# PCB_AMR_Esquematico.net
KiCad netlist of a schematic drawn in EasyEDA
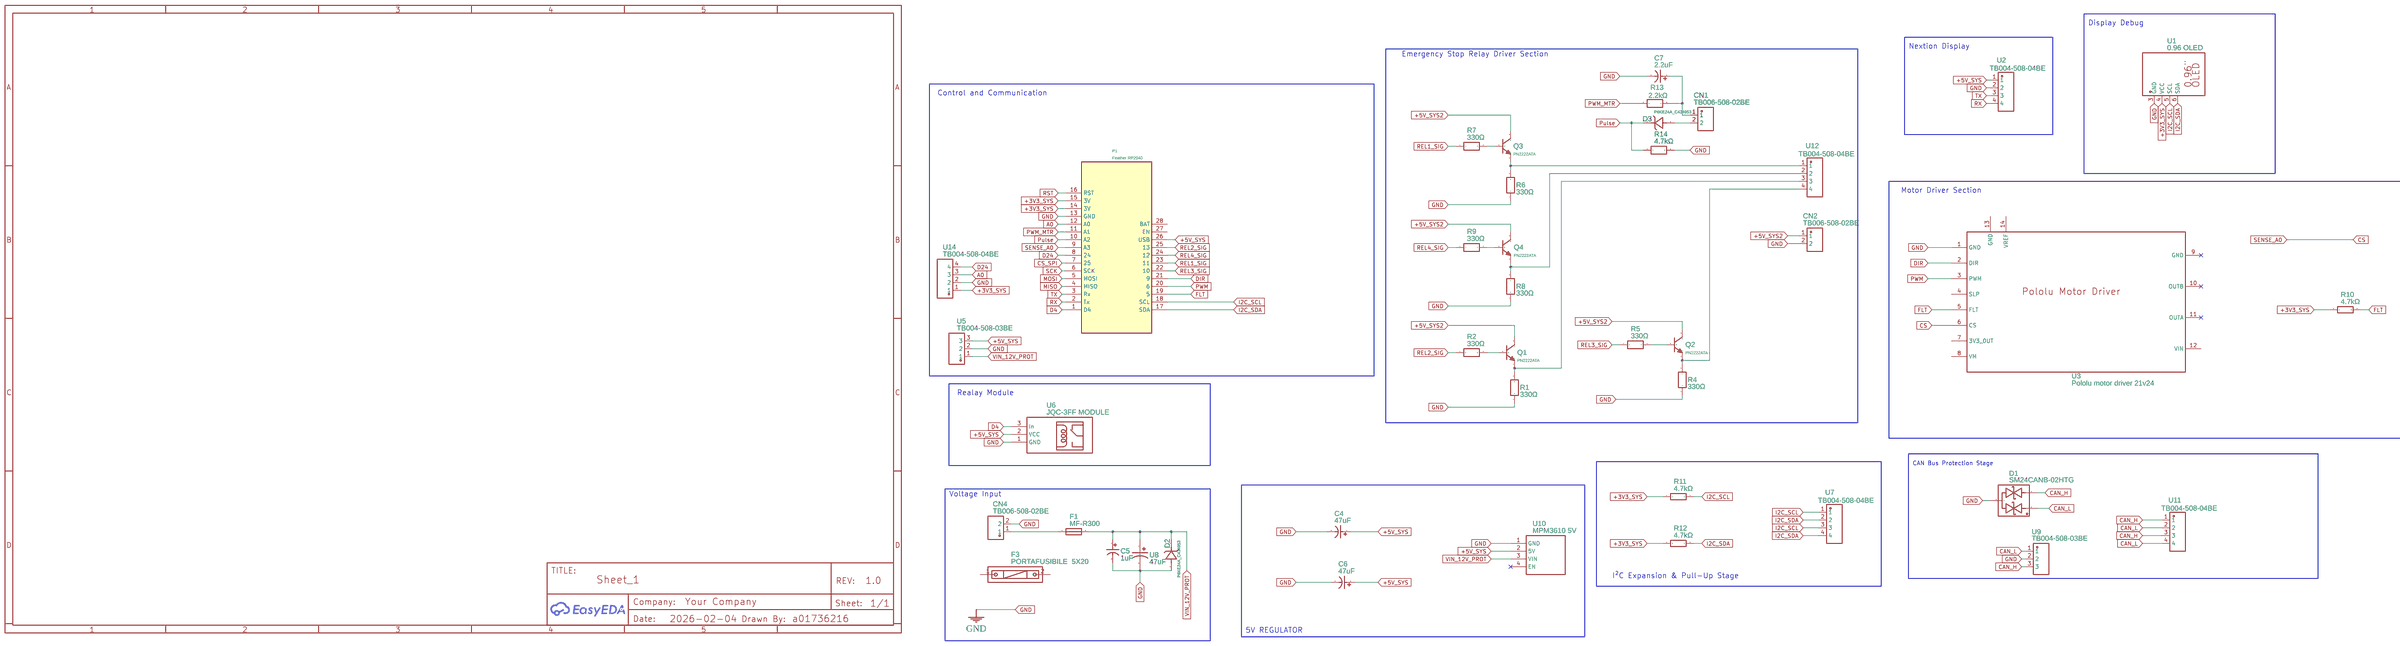
[diagram p0: schematic sheet]

(export (version "E")
  (design (tool "Eeschema 10.0.6"))
  (components
    (comp (ref "C4")
      (value "47uF")
      (fields
        (field (name "Manufacturer Part") "KM476M016D11RR0VH2FP0")
        (field (name "Manufacturer") "Chengx(承兴)")
      )
      (libsource (lib "") (part "47uF 16V Aluminum electrolytic capacitors"))
    )
    (comp (ref "C5")
      (value "1uF")
      (fields
        (field (name "Manufacturer Part") "KM105M250E11RR0VH2FP0")
        (field (name "Manufacturer") "Chengx(承兴)")
      )
      (libsource (lib "") (part "1uF 250V 6.3*11"))
    )
    (comp (ref "C6")
      (value "47uF")
      (fields
        (field (name "Manufacturer Part") "KM476M016D11RR0VH2FP0")
        (field (name "Manufacturer") "Chengx(承兴)")
      )
      (libsource (lib "") (part "47uF 16V Aluminum electrolytic capacitors"))
    )
    (comp (ref "C7")
      (value "2.2uF")
      (fields
        (field (name "Manufacturer Part") "KM476M016D11RR0VH2FP0")
        (field (name "Manufacturer") "Chengx(承兴)")
      )
      (libsource (lib "") (part "47uF 16V Aluminum electrolytic capacitors"))
    )
    (comp (ref "CN1") (value "TB006-508-02BE") (libsource (lib "") (part "TB006-508-02BE_1")))
    (comp (ref "CN2") (value "TB006-508-02BE") (libsource (lib "") (part "TB006-508-02BE_1")))
    (comp (ref "CN4") (value "TB006-508-02BE") (libsource (lib "") (part "TB006-508-02BE")))
    (comp (ref "D1")
      (value "SM24CANB-02HTG")
      (fields (field (name "Manufacturer") "Littelfuse(美国力特)"))
      (libsource (lib "") (part "SM24CANB-02HTG"))
    )
    (comp (ref "D2")
      (value "P6KE24A_C434953")
      (fields (field (name "Manufacturer Part") "P6KE24A") (field (name "Manufacturer") "CREATEK(达晶微)"))
      (libsource (lib "") (part "P6KE24A_C434953_1"))
    )
    (comp (ref "D3")
      (value "P6KE24A_C434953")
      (fields (field (name "Manufacturer Part") "P6KE24A") (field (name "Manufacturer") "CREATEK(达晶微)"))
      (libsource (lib "") (part "P6KE24A_C434953"))
    )
    (comp (ref "F1")
      (value "MF-R300")
      (fields (field (name "Manufacturer") "BOURNS"))
      (libsource (lib "") (part "MF-R300"))
    )
    (comp (ref "F3") (value "PORTAFUSIBILE  5X20") (libsource (lib "") (part "PORTAFUSIBILE  5X20")))
    (comp (ref "P1")
      (value "Feather RP2040")
      (fields (field (name "Manufacturer") "Adafruit"))
      (libsource (lib "") (part "Feather RP2040"))
    )
    (comp (ref "Q1")
      (value "PN2222ATA")
      (fields (field (name "Manufacturer") "onsemi(安森美)"))
      (libsource (lib "") (part "PN2222ATA"))
    )
    (comp (ref "Q2")
      (value "PN2222ATA")
      (fields (field (name "Manufacturer") "onsemi(安森美)"))
      (libsource (lib "") (part "PN2222ATA"))
    )
    (comp (ref "Q3")
      (value "PN2222ATA")
      (fields (field (name "Manufacturer") "onsemi(安森美)"))
      (libsource (lib "") (part "PN2222ATA"))
    )
    (comp (ref "Q4")
      (value "PN2222ATA")
      (fields (field (name "Manufacturer") "onsemi(安森美)"))
      (libsource (lib "") (part "PN2222ATA"))
    )
    (comp (ref "R1")
      (value "330Ω")
      (fields
        (field (name "Manufacturer Part") "RN 1/4W 330R F T/B A1")
        (field (name "Manufacturer") "Tyohm(幸亚电阻)")
      )
      (libsource (lib "") (part "RN 1/4W 330R F T/B A1_1"))
    )
    (comp (ref "R2")
      (value "330Ω")
      (fields
        (field (name "Manufacturer Part") "RN 1/4W 330R F T/B A1")
        (field (name "Manufacturer") "Tyohm(幸亚电阻)")
      )
      (libsource (lib "") (part "RN 1/4W 330R F T/B A1"))
    )
    (comp (ref "R4")
      (value "330Ω")
      (fields
        (field (name "Manufacturer Part") "RN 1/4W 330R F T/B A1")
        (field (name "Manufacturer") "Tyohm(幸亚电阻)")
      )
      (libsource (lib "") (part "RN 1/4W 330R F T/B A1_1"))
    )
    (comp (ref "R5")
      (value "330Ω")
      (fields
        (field (name "Manufacturer Part") "RN 1/4W 330R F T/B A1")
        (field (name "Manufacturer") "Tyohm(幸亚电阻)")
      )
      (libsource (lib "") (part "RN 1/4W 330R F T/B A1"))
    )
    (comp (ref "R6")
      (value "330Ω")
      (fields
        (field (name "Manufacturer Part") "RN 1/4W 330R F T/B A1")
        (field (name "Manufacturer") "Tyohm(幸亚电阻)")
      )
      (libsource (lib "") (part "RN 1/4W 330R F T/B A1_1"))
    )
    (comp (ref "R7")
      (value "330Ω")
      (fields
        (field (name "Manufacturer Part") "RN 1/4W 330R F T/B A1")
        (field (name "Manufacturer") "Tyohm(幸亚电阻)")
      )
      (libsource (lib "") (part "RN 1/4W 330R F T/B A1"))
    )
    (comp (ref "R8")
      (value "330Ω")
      (fields
        (field (name "Manufacturer Part") "RN 1/4W 330R F T/B A1")
        (field (name "Manufacturer") "Tyohm(幸亚电阻)")
      )
      (libsource (lib "") (part "RN 1/4W 330R F T/B A1_1"))
    )
    (comp (ref "R9")
      (value "330Ω")
      (fields
        (field (name "Manufacturer Part") "RN 1/4W 330R F T/B A1")
        (field (name "Manufacturer") "Tyohm(幸亚电阻)")
      )
      (libsource (lib "") (part "RN 1/4W 330R F T/B A1"))
    )
    (comp (ref "R10")
      (value "4.7kΩ")
      (fields
        (field (name "Manufacturer Part") "CF1/4W-4.7KΩ±5% T")
        (field (name "Manufacturer") "CCO(千志电子)")
      )
      (libsource (lib "") (part "CF1/4W-4.7KΩ±5% T52"))
    )
    (comp (ref "R11")
      (value "4.7kΩ")
      (fields
        (field (name "Manufacturer Part") "CF1/4W-4.7KΩ±5% T")
        (field (name "Manufacturer") "CCO(千志电子)")
      )
      (libsource (lib "") (part "CF1/4W-4.7KΩ±5% T52"))
    )
    (comp (ref "R12")
      (value "4.7kΩ")
      (fields
        (field (name "Manufacturer Part") "CF1/4W-4.7KΩ±5% T")
        (field (name "Manufacturer") "CCO(千志电子)")
      )
      (libsource (lib "") (part "CF1/4W-4.7KΩ±5% T52"))
    )
    (comp (ref "R13")
      (value "2.2kΩ")
      (fields
        (field (name "Manufacturer Part") "RN 1/4W 330R F T/B A1")
        (field (name "Manufacturer") "Tyohm(幸亚电阻)")
      )
      (libsource (lib "") (part "RN 1/4W 330R F T/B A1"))
    )
    (comp (ref "R14")
      (value "4.7kΩ")
      (fields
        (field (name "Manufacturer Part") "RN 1/4W 330R F T/B A1")
        (field (name "Manufacturer") "Tyohm(幸亚电阻)")
      )
      (libsource (lib "") (part "RN 1/4W 330R F T/B A1"))
    )
    (comp (ref "U1")
      (value "0.96 OLED")
      (fields
        (field (name "Manufacturer Part") "ZJY096S0700BG01蓝色")
        (field (name "Manufacturer") "AZDelivery")
      )
      (libsource (lib "") (part "0.96 OLED"))
    )
    (comp (ref "U2")
      (value "TB004-508-04BE")
      (fields (field (name "Manufacturer") "CUI"))
      (libsource (lib "") (part "TB004-508-04BE"))
    )
    (comp (ref "U3")
      (value "Pololu motor driver 21v24")
      (libsource (lib "") (part "Pololu motor driver 18v25"))
    )
    (comp (ref "U5")
      (value "TB004-508-03BE")
      (fields (field (name "Manufacturer") "CUI"))
      (libsource (lib "") (part "TB004-508-03BE_1"))
    )
    (comp (ref "U6")
      (value "JQC-3FF MODULE")
      (fields (field (name "Manufacturer Part") "JQC-3FF"))
      (libsource (lib "") (part "JQC-3FF MODULE"))
    )
    (comp (ref "U7")
      (value "TB004-508-04BE")
      (fields (field (name "Manufacturer") "CUI"))
      (libsource (lib "") (part "TB004-508-04BE"))
    )
    (comp (ref "U8")
      (value "47uF")
      (fields (field (name "Manufacturer Part") "25V47uF CD110") (field (name "Manufacturer") "HRK(鸿瑞凯电子)"))
      (libsource (lib "") (part "25V47UF CD110"))
    )
    (comp (ref "U9")
      (value "TB004-508-03BE")
      (fields (field (name "Manufacturer") "CUI"))
      (libsource (lib "") (part "TB004-508-03BE"))
    )
    (comp (ref "U10")
      (value "MPM3610 5V")
      (fields (field (name "Manufacturer Part") "4739") (field (name "Manufacturer") "Adafruit"))
      (libsource (lib "") (part "MPM3610 5V"))
    )
    (comp (ref "U11")
      (value "TB004-508-04BE")
      (fields (field (name "Manufacturer") "CUI"))
      (libsource (lib "") (part "TB004-508-04BE"))
    )
    (comp (ref "U12")
      (value "TB004-508-04BE")
      (fields (field (name "Manufacturer") "CUI"))
      (libsource (lib "") (part "TB004-508-04BE"))
    )
    (comp (ref "U14")
      (value "TB004-508-04BE")
      (fields (field (name "Manufacturer") "CUI"))
      (libsource (lib "") (part "TB004-508-04BE_1"))
    )
  )
  (nets
    (net (code "1") (name "+3V3_SYS") (class "Default")
      (node (ref "P1") (pin "14") (pinfunction "3V_14") (pintype "unspecified"))
      (node (ref "P1") (pin "15") (pinfunction "3V_15") (pintype "unspecified"))
      (node (ref "R10") (pin "1") (pinfunction "1_1") (pintype "unspecified"))
      (node (ref "R11") (pin "1") (pinfunction "1_1") (pintype "unspecified"))
      (node (ref "R12") (pin "1") (pinfunction "1_1") (pintype "unspecified"))
      (node (ref "U1") (pin "4") (pinfunction "VCC_4") (pintype "unspecified"))
      (node (ref "U14") (pin "1") (pinfunction "1_1") (pintype "unspecified"))
    )
    (net (code "2") (name "+5V_SYS") (class "Default")
      (node (ref "C4") (pin "1") (pinfunction "1_1") (pintype "input"))
      (node (ref "C6") (pin "1") (pinfunction "1_1") (pintype "input"))
      (node (ref "P1") (pin "26") (pinfunction "USB_26") (pintype "unspecified"))
      (node (ref "U10") (pin "2") (pinfunction "5V_2") (pintype "unspecified"))
      (node (ref "U2") (pin "1") (pinfunction "1_1") (pintype "unspecified"))
      (node (ref "U5") (pin "3") (pinfunction "3_3") (pintype "unspecified"))
      (node (ref "U6") (pin "2") (pinfunction "VCC_2") (pintype "unspecified"))
    )
    (net (code "3") (name "+5V_SYS2") (class "Default")
      (node (ref "CN2") (pin "1") (pinfunction "1_1") (pintype "unspecified"))
      (node (ref "Q1") (pin "3") (pinfunction "C_3") (pintype "unspecified"))
      (node (ref "Q2") (pin "3") (pinfunction "C_3") (pintype "unspecified"))
      (node (ref "Q3") (pin "3") (pinfunction "C_3") (pintype "unspecified"))
      (node (ref "Q4") (pin "3") (pinfunction "C_3") (pintype "unspecified"))
    )
    (net (code "4") (name "A0") (class "Default")
      (node (ref "P1") (pin "12") (pinfunction "A0_12") (pintype "unspecified"))
      (node (ref "U14") (pin "3") (pinfunction "3_3") (pintype "unspecified"))
    )
    (net (code "5") (name "CAN_H") (class "Default")
      (node (ref "D1") (pin "2") (pinfunction "2_2") (pintype "unspecified"))
      (node (ref "U11") (pin "1") (pinfunction "1_1") (pintype "unspecified"))
      (node (ref "U11") (pin "3") (pinfunction "3_3") (pintype "unspecified"))
      (node (ref "U9") (pin "3") (pinfunction "3_3") (pintype "unspecified"))
    )
    (net (code "6") (name "CAN_L") (class "Default")
      (node (ref "D1") (pin "1") (pinfunction "1_1") (pintype "unspecified"))
      (node (ref "U11") (pin "2") (pinfunction "2_2") (pintype "unspecified"))
      (node (ref "U11") (pin "4") (pinfunction "4_4") (pintype "unspecified"))
      (node (ref "U9") (pin "1") (pinfunction "1_1") (pintype "unspecified"))
    )
    (net (code "7") (name "CS") (class "Default")
      (node (ref "P1") (pin "9") (pinfunction "A3_9") (pintype "unspecified"))
      (node (ref "U3") (pin "6") (pinfunction "CS_6") (pintype "unspecified"))
    )
    (net (code "8") (name "CS_SPI") (class "Default")
      (node (ref "P1") (pin "7") (pinfunction "25_7") (pintype "unspecified"))
    )
    (net (code "9") (name "D4") (class "Default")
      (node (ref "P1") (pin "1") (pinfunction "D4_1") (pintype "unspecified"))
      (node (ref "U6") (pin "3") (pinfunction "In_3") (pintype "unspecified"))
    )
    (net (code "10") (name "D24") (class "Default")
      (node (ref "P1") (pin "8") (pinfunction "24_8") (pintype "unspecified"))
      (node (ref "U14") (pin "4") (pinfunction "4_4") (pintype "unspecified"))
    )
    (net (code "11") (name "DIR") (class "Default")
      (node (ref "P1") (pin "21") (pinfunction "9_21") (pintype "unspecified"))
      (node (ref "U3") (pin "2") (pinfunction "DIR_2") (pintype "unspecified"))
    )
    (net (code "12") (name "FLT") (class "Default")
      (node (ref "P1") (pin "19") (pinfunction "5_19") (pintype "unspecified"))
      (node (ref "R10") (pin "2") (pinfunction "2_2") (pintype "unspecified"))
      (node (ref "U3") (pin "5") (pinfunction "FLT_5") (pintype "unspecified"))
    )
    (net (code "13") (name "GND") (class "Default")
      (node (ref "C4") (pin "2") (pinfunction "2_2") (pintype "input"))
      (node (ref "C5") (pin "2") (pinfunction "2_2") (pintype "input"))
      (node (ref "C6") (pin "2") (pinfunction "2_2") (pintype "input"))
      (node (ref "C7") (pin "2") (pinfunction "2_2") (pintype "input"))
      (node (ref "CN2") (pin "2") (pinfunction "2_2") (pintype "unspecified"))
      (node (ref "CN4") (pin "2") (pinfunction "2_2") (pintype "unspecified"))
      (node (ref "D1") (pin "3") (pinfunction "3_3") (pintype "unspecified"))
      (node (ref "D2") (pin "2") (pinfunction "A_2") (pintype "unspecified"))
      (node (ref "P1") (pin "13") (pinfunction "GND_13") (pintype "unspecified"))
      (node (ref "R1") (pin "1") (pinfunction "1_1") (pintype "unspecified"))
      (node (ref "R14") (pin "2") (pinfunction "2_2") (pintype "unspecified"))
      (node (ref "R4") (pin "1") (pinfunction "1_1") (pintype "unspecified"))
      (node (ref "R6") (pin "1") (pinfunction "1_1") (pintype "unspecified"))
      (node (ref "R8") (pin "1") (pinfunction "1_1") (pintype "unspecified"))
      (node (ref "U1") (pin "3") (pinfunction "GND_3") (pintype "unspecified"))
      (node (ref "U10") (pin "1") (pinfunction "GND_1") (pintype "unspecified"))
      (node (ref "U14") (pin "2") (pinfunction "2_2") (pintype "unspecified"))
      (node (ref "U2") (pin "2") (pinfunction "2_2") (pintype "unspecified"))
      (node (ref "U3") (pin "1") (pinfunction "GND_1") (pintype "unspecified"))
      (node (ref "U5") (pin "2") (pinfunction "2_2") (pintype "unspecified"))
      (node (ref "U6") (pin "1") (pinfunction "GND_1") (pintype "unspecified"))
      (node (ref "U8") (pin "2") (pinfunction "2_2") (pintype "unspecified"))
      (node (ref "U9") (pin "2") (pinfunction "2_2") (pintype "unspecified"))
    )
    (net (code "14") (name "I2C_SCL") (class "Default")
      (node (ref "P1") (pin "18") (pinfunction "SCL_18") (pintype "unspecified"))
      (node (ref "R11") (pin "2") (pinfunction "2_2") (pintype "unspecified"))
      (node (ref "U1") (pin "5") (pinfunction "SCL_5") (pintype "unspecified"))
      (node (ref "U7") (pin "1") (pinfunction "1_1") (pintype "unspecified"))
      (node (ref "U7") (pin "3") (pinfunction "3_3") (pintype "unspecified"))
    )
    (net (code "15") (name "I2C_SDA") (class "Default")
      (node (ref "P1") (pin "17") (pinfunction "SDA_17") (pintype "unspecified"))
      (node (ref "R12") (pin "2") (pinfunction "2_2") (pintype "unspecified"))
      (node (ref "U1") (pin "6") (pinfunction "SDA_6") (pintype "unspecified"))
      (node (ref "U7") (pin "2") (pinfunction "2_2") (pintype "unspecified"))
      (node (ref "U7") (pin "4") (pinfunction "4_4") (pintype "unspecified"))
    )
    (net (code "16") (name "MISO") (class "Default")
      (node (ref "P1") (pin "4") (pinfunction "MISO_4") (pintype "unspecified"))
    )
    (net (code "17") (name "MOSI") (class "Default")
      (node (ref "P1") (pin "5") (pinfunction "MOSI_5") (pintype "unspecified"))
    )
    (net (code "18") (name "Net-(C7-Pad1)") (class "Default")
      (node (ref "C7") (pin "1") (pinfunction "1_1") (pintype "input"))
      (node (ref "CN1") (pin "1") (pinfunction "1_1") (pintype "unspecified"))
      (node (ref "R13") (pin "2") (pinfunction "2_2") (pintype "unspecified"))
    )
    (net (code "19") (name "Net-(CN4-Pad1)") (class "Default")
      (node (ref "CN4") (pin "1") (pinfunction "1_1") (pintype "unspecified"))
      (node (ref "F1") (pin "1") (pinfunction "1_1") (pintype "unspecified"))
    )
    (net (code "20") (name "Net-(D3-A)") (class "Default")
      (node (ref "CN1") (pin "2") (pinfunction "2_2") (pintype "unspecified"))
      (node (ref "D3") (pin "2") (pinfunction "A_2") (pintype "unspecified"))
    )
    (net (code "21") (name "Net-(Q1-B)") (class "Default")
      (node (ref "Q1") (pin "2") (pinfunction "B_2") (pintype "unspecified"))
      (node (ref "R2") (pin "2") (pinfunction "2_2") (pintype "unspecified"))
    )
    (net (code "22") (name "Net-(Q1-E)") (class "Default")
      (node (ref "Q1") (pin "1") (pinfunction "E_1") (pintype "unspecified"))
      (node (ref "R1") (pin "2") (pinfunction "2_2") (pintype "unspecified"))
      (node (ref "U12") (pin "3") (pinfunction "3_3") (pintype "unspecified"))
    )
    (net (code "23") (name "Net-(Q2-B)") (class "Default")
      (node (ref "Q2") (pin "2") (pinfunction "B_2") (pintype "unspecified"))
      (node (ref "R5") (pin "2") (pinfunction "2_2") (pintype "unspecified"))
    )
    (net (code "24") (name "Net-(Q2-E)") (class "Default")
      (node (ref "Q2") (pin "1") (pinfunction "E_1") (pintype "unspecified"))
      (node (ref "R4") (pin "2") (pinfunction "2_2") (pintype "unspecified"))
      (node (ref "U12") (pin "4") (pinfunction "4_4") (pintype "unspecified"))
    )
    (net (code "25") (name "Net-(Q3-B)") (class "Default")
      (node (ref "Q3") (pin "2") (pinfunction "B_2") (pintype "unspecified"))
      (node (ref "R7") (pin "2") (pinfunction "2_2") (pintype "unspecified"))
    )
    (net (code "26") (name "Net-(Q3-E)") (class "Default")
      (node (ref "Q3") (pin "1") (pinfunction "E_1") (pintype "unspecified"))
      (node (ref "R6") (pin "2") (pinfunction "2_2") (pintype "unspecified"))
      (node (ref "U12") (pin "1") (pinfunction "1_1") (pintype "unspecified"))
    )
    (net (code "27") (name "Net-(Q4-B)") (class "Default")
      (node (ref "Q4") (pin "2") (pinfunction "B_2") (pintype "unspecified"))
      (node (ref "R9") (pin "2") (pinfunction "2_2") (pintype "unspecified"))
    )
    (net (code "28") (name "Net-(Q4-E)") (class "Default")
      (node (ref "Q4") (pin "1") (pinfunction "E_1") (pintype "unspecified"))
      (node (ref "R8") (pin "2") (pinfunction "2_2") (pintype "unspecified"))
      (node (ref "U12") (pin "2") (pinfunction "2_2") (pintype "unspecified"))
    )
    (net (code "29") (name "PWM") (class "Default")
      (node (ref "P1") (pin "20") (pinfunction "6_20") (pintype "unspecified"))
      (node (ref "U3") (pin "3") (pinfunction "PWM_3") (pintype "unspecified"))
    )
    (net (code "30") (name "PWM_MTR") (class "Default")
      (node (ref "P1") (pin "11") (pinfunction "A1_11") (pintype "unspecified"))
      (node (ref "R13") (pin "1") (pinfunction "1_1") (pintype "unspecified"))
    )
    (net (code "31") (name "Pulse") (class "Default")
      (node (ref "D3") (pin "1") (pinfunction "C_1") (pintype "unspecified"))
      (node (ref "P1") (pin "10") (pinfunction "A2_10") (pintype "unspecified"))
      (node (ref "R14") (pin "1") (pinfunction "1_1") (pintype "unspecified"))
    )
    (net (code "32") (name "REL1_SIG") (class "Default")
      (node (ref "P1") (pin "23") (pinfunction "11_23") (pintype "unspecified"))
      (node (ref "R7") (pin "1") (pinfunction "1_1") (pintype "unspecified"))
    )
    (net (code "33") (name "REL2_SIG") (class "Default")
      (node (ref "P1") (pin "25") (pinfunction "13_25") (pintype "unspecified"))
      (node (ref "R2") (pin "1") (pinfunction "1_1") (pintype "unspecified"))
    )
    (net (code "34") (name "REL3_SIG") (class "Default")
      (node (ref "P1") (pin "22") (pinfunction "10_22") (pintype "unspecified"))
      (node (ref "R5") (pin "1") (pinfunction "1_1") (pintype "unspecified"))
    )
    (net (code "35") (name "REL4_SIG") (class "Default")
      (node (ref "P1") (pin "24") (pinfunction "12_24") (pintype "unspecified"))
      (node (ref "R9") (pin "1") (pinfunction "1_1") (pintype "unspecified"))
    )
    (net (code "36") (name "RST") (class "Default")
      (node (ref "P1") (pin "16") (pinfunction "RST_16") (pintype "unspecified"))
    )
    (net (code "37") (name "RX") (class "Default")
      (node (ref "P1") (pin "2") (pinfunction "Tx_2") (pintype "unspecified"))
      (node (ref "U2") (pin "4") (pinfunction "4_4") (pintype "unspecified"))
    )
    (net (code "38") (name "SCK") (class "Default")
      (node (ref "P1") (pin "6") (pinfunction "SCK_6") (pintype "unspecified"))
    )
    (net (code "39") (name "TX") (class "Default")
      (node (ref "P1") (pin "3") (pinfunction "Rx_3") (pintype "unspecified"))
      (node (ref "U2") (pin "3") (pinfunction "3_3") (pintype "unspecified"))
    )
    (net (code "40") (name "VIN_12V_PROT") (class "Default")
      (node (ref "C5") (pin "1") (pinfunction "1_1") (pintype "input"))
      (node (ref "D2") (pin "1") (pinfunction "C_1") (pintype "unspecified"))
      (node (ref "F1") (pin "2") (pinfunction "2_2") (pintype "unspecified"))
      (node (ref "U10") (pin "3") (pinfunction "VIN_3") (pintype "unspecified"))
      (node (ref "U5") (pin "1") (pinfunction "1_1") (pintype "unspecified"))
      (node (ref "U8") (pin "1") (pinfunction "1_1") (pintype "unspecified"))
    )
    (net (code "41") (name "unconnected-(F3-Pad1)") (class "Default")
      (node (ref "F3") (pin "1") (pinfunction "1_1") (pintype "unspecified"))
    )
    (net (code "42") (name "unconnected-(F3-Pad2)") (class "Default")
      (node (ref "F3") (pin "2") (pinfunction "2_2") (pintype "unspecified"))
    )
    (net (code "43") (name "unconnected-(P1-BAT-Pad28)") (class "Default")
      (node (ref "P1") (pin "28") (pinfunction "BAT_28") (pintype "unspecified"))
    )
    (net (code "44") (name "unconnected-(P1-EN-Pad27)") (class "Default")
      (node (ref "P1") (pin "27") (pinfunction "EN_27") (pintype "unspecified"))
    )
    (net (code "45") (name "unconnected-(U3-3V3_0UT-Pad7)") (class "Default")
      (node (ref "U3") (pin "7") (pinfunction "3V3_0UT_7") (pintype "unspecified"))
    )
    (net (code "46") (name "unconnected-(U3-GND-Pad9)") (class "Default")
      (node (ref "U3") (pin "9") (pinfunction "GND_9") (pintype "unspecified+no_connect"))
    )
    (net (code "47") (name "unconnected-(U3-GND-Pad13)") (class "Default")
      (node (ref "U3") (pin "13") (pinfunction "GND_13") (pintype "unspecified"))
    )
    (net (code "48") (name "unconnected-(U3-OUTA-Pad11)") (class "Default")
      (node (ref "U3") (pin "11") (pinfunction "OUTA_11") (pintype "unspecified+no_connect"))
    )
    (net (code "49") (name "unconnected-(U3-OUTB-Pad10)") (class "Default")
      (node (ref "U3") (pin "10") (pinfunction "OUTB_10") (pintype "unspecified+no_connect"))
    )
    (net (code "50") (name "unconnected-(U3-SLP-Pad4)") (class "Default")
      (node (ref "U3") (pin "4") (pinfunction "SLP_4") (pintype "unspecified"))
    )
    (net (code "51") (name "unconnected-(U3-VIN-Pad12)") (class "Default")
      (node (ref "U3") (pin "12") (pinfunction "VIN_12") (pintype "unspecified"))
    )
    (net (code "52") (name "unconnected-(U3-VM-Pad8)") (class "Default")
      (node (ref "U3") (pin "8") (pinfunction "VM_8") (pintype "unspecified"))
    )
    (net (code "53") (name "unconnected-(U3-VREF-Pad14)") (class "Default")
      (node (ref "U3") (pin "14") (pinfunction "VREF_14") (pintype "unspecified"))
    )
    (net (code "54") (name "unconnected-(U10-EN-Pad4)") (class "Default")
      (node (ref "U10") (pin "4") (pinfunction "EN_4") (pintype "unspecified+no_connect"))
    )
  )
)
